# DSO_Clock.net
KiCad netlist of a schematic drawn in Altium Designer
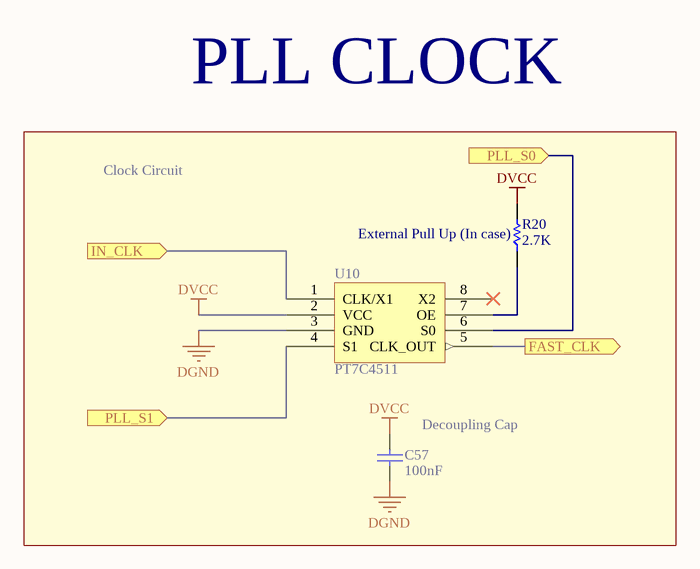
[diagram p0: DSO_Clock.SchDoc]

(export (version "E")
  (design (tool "Eeschema 10.0.6"))
  (components
    (comp (ref "C57")
      (value "100nF")
      (footprint "0805C")
      (description "Capacitor")
      (fields (field (name "REVIEWED BY") "RM - 2018/08/05"))
      (libsource (lib "DSO") (part "C"))
    )
    (comp (ref "R20")
      (value "2.7K")
      (footprint "0805")
      (description "Resistor")
      (fields (field (name "REVIEWED BY") "RM - 2018/08/05"))
      (libsource (lib "DSO") (part "R"))
    )
    (comp (ref "U10")
      (value "PT7C4511")
      (footprint "SOIC-8")
      (description "PLL Clock Multiplier")
      (fields (field (name "REVIEWED BY") "RM - 2018/08/05"))
      (libsource (lib "DSO") (part "PT7C4511"))
    )
  )
  (nets
    (net (code "1") (name "/FAST_CLK") (class "Default")
      (node (ref "U10") (pin "5") (pinfunction "CLK_OUT_5") (pintype "output"))
    )
    (net (code "2") (name "/IN_CLK") (class "Default")
      (node (ref "U10") (pin "1") (pinfunction "CLK/X1_1") (pintype "passive"))
    )
    (net (code "3") (name "/PLL_S0") (class "Default")
      (node (ref "U10") (pin "6") (pinfunction "S0_6") (pintype "passive"))
    )
    (net (code "4") (name "/PLL_S1") (class "Default")
      (node (ref "U10") (pin "4") (pinfunction "S1_4") (pintype "passive"))
    )
    (net (code "5") (name "DGND") (class "Default")
      (node (ref "C57") (pin "2") (pinfunction "2_2") (pintype "passive"))
      (node (ref "U10") (pin "3") (pinfunction "GND_3") (pintype "passive"))
    )
    (net (code "6") (name "DVCC") (class "Default")
      (node (ref "C57") (pin "1") (pinfunction "1_1") (pintype "passive"))
      (node (ref "R20") (pin "2") (pintype "passive"))
      (node (ref "U10") (pin "2") (pinfunction "VCC_2") (pintype "passive"))
    )
    (net (code "7") (name "Net-(U10-OE)") (class "Default")
      (node (ref "R20") (pin "1") (pintype "passive"))
      (node (ref "U10") (pin "7") (pinfunction "OE_7") (pintype "passive"))
    )
    (net (code "8") (name "unconnected-(U10-X2-Pad8)") (class "Default")
      (node (ref "U10") (pin "8") (pinfunction "X2_8") (pintype "passive+no_connect"))
    )
  )
)
